# Adapter-TenX-Direct.net
KiCad netlist of a schematic drawn in EAGLE
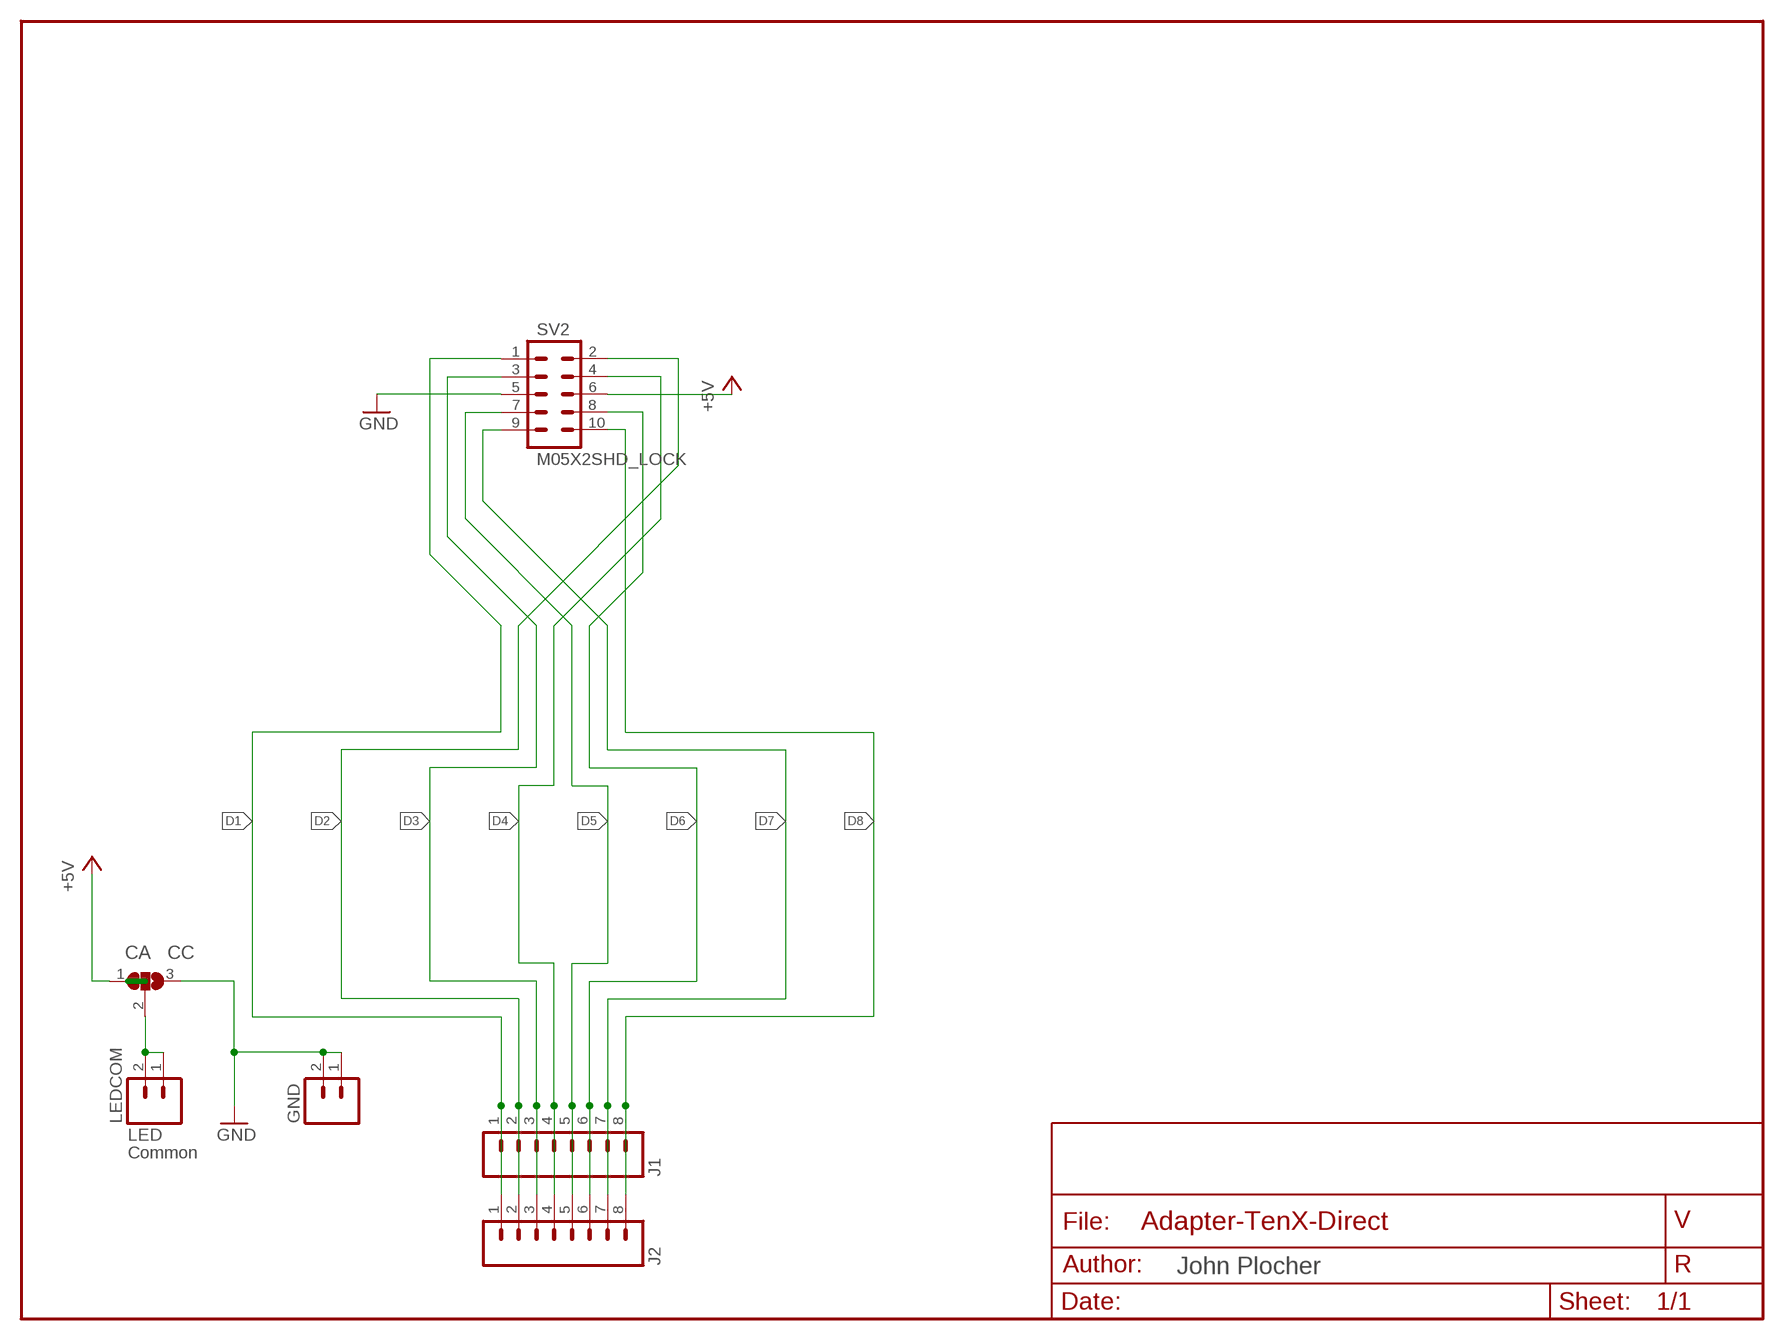
[diagram p0: schematic, sheet 1]

(export (version "E")
  (design (tool "Eeschema 10.0.6"))
  (components
    (comp (ref "GND")
      (value "M02POLAR_LOCK")
      (footprint "eagle-import:MOLEX-1X2_LOCK")
      (libsource (lib "eagle-import") (part "M02POLAR_LOCK"))
    )
    (comp (ref "J1")
      (value "CONNECTOR-M08LOCK_LONGPADS")
      (footprint "eagle-import:1X08_LOCK_LONGPADS")
      (libsource (lib "eagle-import") (part "CONNECTOR-M08LOCK_LONGPADS"))
    )
    (comp (ref "J2")
      (value "CONNECTOR-M081.56-M")
      (footprint "eagle-import:KK-156-8-M")
      (libsource (lib "eagle-import") (part "CONNECTOR-M081.56-M"))
    )
    (comp (ref "LEDCOM")
      (value "M02POLAR_LOCK")
      (footprint "eagle-import:MOLEX-1X2_LOCK")
      (libsource (lib "eagle-import") (part "M02POLAR_LOCK"))
    )
    (comp (ref "P1")
      (value "CA CC")
      (footprint "eagle-import:3P-SMD-2X4.8")
      (libsource (lib "eagle-import") (part "PAD-SOLDERJUMPER-2WAYT"))
    )
    (comp (ref "SV2")
      (value "M05X2SHD_LOCK")
      (footprint "eagle-import:2X5-SHROUDED_LOCK")
      (libsource (lib "eagle-import") (part "M05X2SHD_LOCK"))
    )
  )
  (nets
    (net (code "1") (name "+5V") (class "Default")
      (node (ref "P1") (pin "1") (pinfunction "1_1") (pintype "passive"))
      (node (ref "SV2") (pin "6") (pinfunction "6_6") (pintype "passive"))
    )
    (net (code "2") (name "D1") (class "Default")
      (node (ref "J1") (pin "1") (pinfunction "1_1") (pintype "passive"))
      (node (ref "J2") (pin "1") (pinfunction "1_1") (pintype "passive"))
      (node (ref "SV2") (pin "1") (pinfunction "1_1") (pintype "passive"))
    )
    (net (code "3") (name "D2") (class "Default")
      (node (ref "J1") (pin "2") (pinfunction "2_2") (pintype "passive"))
      (node (ref "J2") (pin "2") (pinfunction "2_2") (pintype "passive"))
      (node (ref "SV2") (pin "2") (pinfunction "2_2") (pintype "passive"))
    )
    (net (code "4") (name "D3") (class "Default")
      (node (ref "J1") (pin "3") (pinfunction "3_3") (pintype "passive"))
      (node (ref "J2") (pin "3") (pinfunction "3_3") (pintype "passive"))
      (node (ref "SV2") (pin "3") (pinfunction "3_3") (pintype "passive"))
    )
    (net (code "5") (name "D4") (class "Default")
      (node (ref "J1") (pin "4") (pinfunction "4_4") (pintype "passive"))
      (node (ref "J2") (pin "4") (pinfunction "4_4") (pintype "passive"))
      (node (ref "SV2") (pin "4") (pinfunction "4_4") (pintype "passive"))
    )
    (net (code "6") (name "D5") (class "Default")
      (node (ref "J1") (pin "5") (pinfunction "5_5") (pintype "passive"))
      (node (ref "J2") (pin "5") (pinfunction "5_5") (pintype "passive"))
      (node (ref "SV2") (pin "7") (pinfunction "7_7") (pintype "passive"))
    )
    (net (code "7") (name "D6") (class "Default")
      (node (ref "J1") (pin "6") (pinfunction "6_6") (pintype "passive"))
      (node (ref "J2") (pin "6") (pinfunction "6_6") (pintype "passive"))
      (node (ref "SV2") (pin "8") (pinfunction "8_8") (pintype "passive"))
    )
    (net (code "8") (name "D7") (class "Default")
      (node (ref "J1") (pin "7") (pinfunction "7_7") (pintype "passive"))
      (node (ref "J2") (pin "7") (pinfunction "7_7") (pintype "passive"))
      (node (ref "SV2") (pin "9") (pinfunction "9_9") (pintype "passive"))
    )
    (net (code "9") (name "D8") (class "Default")
      (node (ref "J1") (pin "8") (pinfunction "8_8") (pintype "passive"))
      (node (ref "J2") (pin "8") (pinfunction "8_8") (pintype "passive"))
      (node (ref "SV2") (pin "10") (pinfunction "10_10") (pintype "passive"))
    )
    (net (code "10") (name "GND") (class "Default")
      (node (ref "GND") (pin "1") (pinfunction "1_1") (pintype "passive"))
      (node (ref "GND") (pin "2") (pinfunction "2_2") (pintype "passive"))
      (node (ref "P1") (pin "3") (pinfunction "3_3") (pintype "passive"))
      (node (ref "SV2") (pin "5") (pinfunction "5_5") (pintype "passive"))
    )
    (net (code "11") (name "Net-(LEDCOM-Pad1)") (class "Default")
      (node (ref "LEDCOM") (pin "1") (pinfunction "1_1") (pintype "passive"))
      (node (ref "LEDCOM") (pin "2") (pinfunction "2_2") (pintype "passive"))
      (node (ref "P1") (pin "2") (pinfunction "2_2") (pintype "passive"))
    )
  )
)
